# Flash.net
KiCad netlist of a schematic drawn in Altium Designer
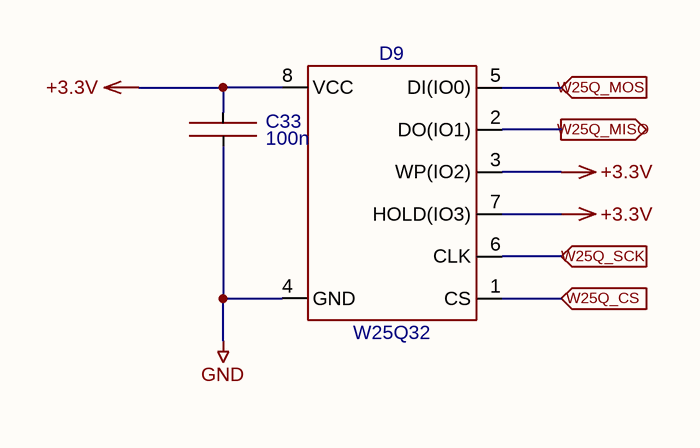
[diagram p0: Flash.SchDoc]

(export (version "E")
  (design (tool "Eeschema 10.0.6"))
  (components
    (comp (ref "C33")
      (value "100n")
      (footprint "CAPC1608X09N")
      (description "GRM188R71E104KA01D")
      (libsource (lib "Capasitors") (part "C0603-100n-25V-X7R-10%"))
    )
    (comp (ref "D9")
      (value "W25Q32")
      (footprint "WINBOND ST 8-Pin VSOP 208-mil")
      (libsource (lib "Integrated Circuits") (part "W25Q32BVSSIG"))
    )
  )
  (nets
    (net (code "1") (name "+3.3V") (class "Default")
      (node (ref "C33") (pin "2") (pinfunction "2_2") (pintype "passive"))
      (node (ref "D9") (pin "3") (pinfunction "WP(IO2)_3") (pintype "passive"))
      (node (ref "D9") (pin "7") (pinfunction "HOLD(IO3)_7") (pintype "passive"))
      (node (ref "D9") (pin "8") (pinfunction "VCC_8") (pintype "passive"))
    )
    (net (code "2") (name "/W25Q_CS") (class "Default")
      (node (ref "D9") (pin "1") (pinfunction "CS_1") (pintype "passive"))
    )
    (net (code "3") (name "/W25Q_MISO") (class "Default")
      (node (ref "D9") (pin "2") (pinfunction "DO(IO1)_2") (pintype "passive"))
    )
    (net (code "4") (name "/W25Q_MOSI") (class "Default")
      (node (ref "D9") (pin "5") (pinfunction "DI(IO0)_5") (pintype "passive"))
    )
    (net (code "5") (name "/W25Q_SCK") (class "Default")
      (node (ref "D9") (pin "6") (pinfunction "CLK_6") (pintype "passive"))
    )
    (net (code "6") (name "GND") (class "Default")
      (node (ref "C33") (pin "1") (pinfunction "1_1") (pintype "passive"))
      (node (ref "D9") (pin "4") (pinfunction "GND_4") (pintype "passive"))
    )
  )
)
